# 10_-MAIN_POWER.net
KiCad netlist of a schematic drawn in Altium Designer
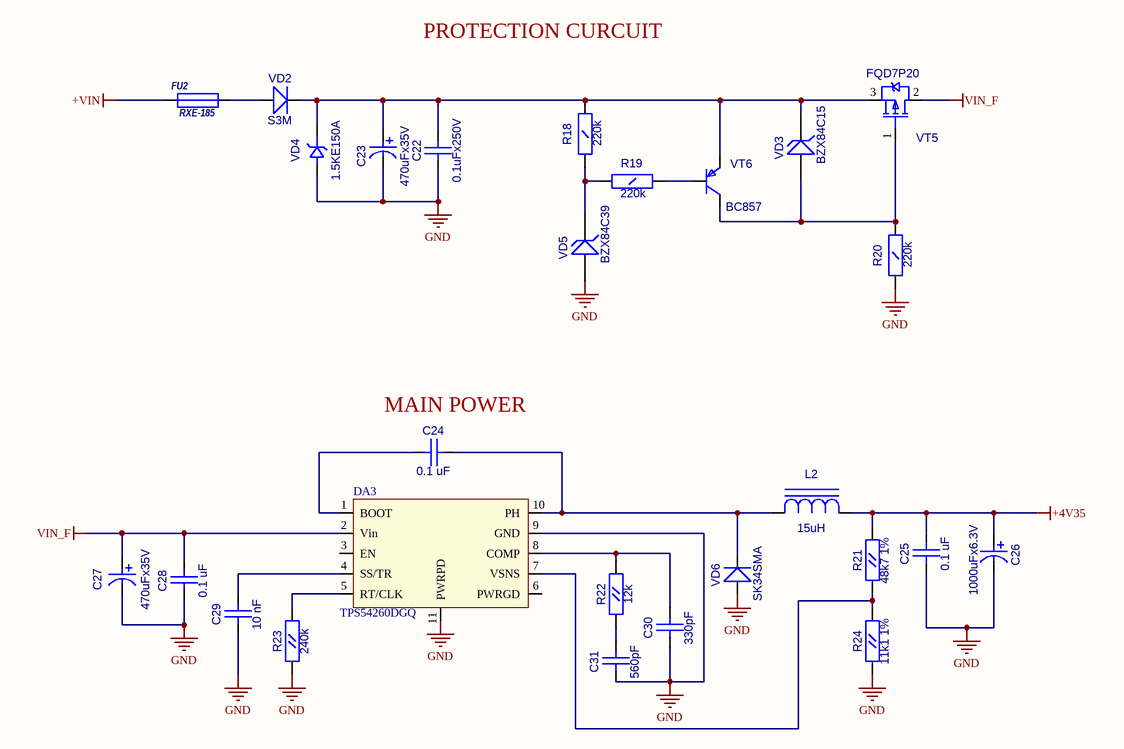
[diagram p0: [10]-MAIN_POWER.SchDoc]

(export (version "E")
  (design (tool "Eeschema 10.0.6"))
  (components
    (comp (ref "C22")
      (value "0.1uFx250V")
      (footprint "CC1206")
      (description "CC1206")
      (libsource (lib "gprs_modem_2") (part "CC1206"))
    )
    (comp (ref "C23")
      (value "470uFx35V")
      (footprint "CC16X10_CAP0.5(1)(Primary)")
      (description "CAP0.5(1)")
      (libsource (lib "gprs_modem_2") (part "CAP0.5(1)"))
    )
    (comp (ref "C24")
      (value "0.1 uF")
      (footprint "CC0603")
      (description "CC0603")
      (libsource (lib "gprs_modem_2") (part "CC0603"))
    )
    (comp (ref "C25")
      (value "0.1 uF")
      (footprint "CC0603")
      (description "CC0603")
      (libsource (lib "gprs_modem_2") (part "CC0603"))
    )
    (comp (ref "C26")
      (value "1000uFx6.3V")
      (footprint "CC8X3.5")
      (description "CAP0.35")
      (libsource (lib "gprs_modem_2") (part "CAP0.35"))
    )
    (comp (ref "C27")
      (value "470uFx35V")
      (footprint "CC16X10_CAP0.5(1)(Primary)")
      (description "CAP0.5(1)")
      (libsource (lib "gprs_modem_2") (part "CAP0.5(1)"))
    )
    (comp (ref "C28")
      (value "0.1 uF")
      (footprint "CC0603")
      (description "CC0603")
      (libsource (lib "gprs_modem_2") (part "CC0603"))
    )
    (comp (ref "C29")
      (value "10 nF")
      (footprint "CC0603")
      (description "CC0603")
      (libsource (lib "gprs_modem_2") (part "CC0603"))
    )
    (comp (ref "C30")
      (value "330pF")
      (footprint "CC0603")
      (description "CC0603")
      (libsource (lib "gprs_modem_2") (part "CC0603"))
    )
    (comp (ref "C31")
      (value "560pF")
      (footprint "CC0603")
      (description "CC0603")
      (libsource (lib "gprs_modem_2") (part "CC0603"))
    )
    (comp (ref "DA3")
      (value "TPS54260DGQ")
      (footprint "S-PDSO-G10")
      (libsource (lib "gprs_modem_2") (part "TPS54260DGQ"))
    )
    (comp (ref "FU2") (value "RXE-185") (footprint "RXE-185") (libsource (lib "fizik_lib") (part "RXE-185")))
    (comp (ref "L2")
      (value "15uH")
      (footprint "SDR0805")
      (description "SDR0805")
      (libsource (lib "gprs_modem_2") (part "SDR0805"))
    )
    (comp (ref "R18")
      (value "220k")
      (footprint "RC1206")
      (description "RC1206")
      (libsource (lib "fizik_lib") (part "RC1206"))
    )
    (comp (ref "R19")
      (value "220k")
      (footprint "RC1206")
      (description "RC1206")
      (libsource (lib "fizik_lib") (part "RC1206"))
    )
    (comp (ref "R20")
      (value "220k")
      (footprint "RC1206")
      (description "RC1206")
      (libsource (lib "fizik_lib") (part "RC1206"))
    )
    (comp (ref "R21")
      (value "48k7 1%")
      (footprint "RC0603")
      (description "RC0603")
      (libsource (lib "gprs_modem_2") (part "RC0603"))
    )
    (comp (ref "R22")
      (value "12k")
      (footprint "RC0603")
      (description "RC0603")
      (libsource (lib "gprs_modem_2") (part "RC0603"))
    )
    (comp (ref "R23")
      (value "240k")
      (footprint "RC0603")
      (description "RC0603")
      (libsource (lib "gprs_modem_2") (part "RC0603"))
    )
    (comp (ref "R24")
      (value "11k1 1%")
      (footprint "RC0603")
      (description "RC0603")
      (libsource (lib "gprs_modem_2") (part "RC0603"))
    )
    (comp (ref "VD2")
      (value "S3M")
      (footprint "SMC")
      (description "Schottky Rectifier")
      (libsource (lib "fizik_lib") (part "S3A"))
    )
    (comp (ref "VD3")
      (value "BZX84C15")
      (footprint "SOT-23(123)")
      (description "Zener Voltage Regulator Diode")
      (libsource (lib "fizik_lib") (part "BZX84"))
    )
    (comp (ref "VD4")
      (value "1.5KE150A")
      (footprint "DO-201")
      (description "1.5KE")
      (libsource (lib "gprs_modem") (part "1.5KE"))
    )
    (comp (ref "VD5")
      (value "BZX84C39")
      (footprint "SOT-23(123)")
      (description "Zener Voltage Regulator Diode")
      (libsource (lib "fizik_lib") (part "BZX84"))
    )
    (comp (ref "VD6")
      (value "SK34SMA")
      (footprint "SMA")
      (description "Schottky Rectifier")
      (libsource (lib "gprs_modem") (part "SK34SMA"))
    )
    (comp (ref "VT5")
      (value "FQD7P20")
      (footprint "D-PAK(TO-252AA)")
      (description "HEXFET Power MOSFET")
      (libsource (lib "gprs_modem_2") (part "IRFR9220"))
    )
    (comp (ref "VT6")
      (value "BC857")
      (footprint "SOT-23(123)")
      (description "PNP 100ma transistor")
      (libsource (lib "gprs_modem_2") (part "BC857B"))
    )
  )
  (nets
    (net (code "1") (name "+4V35") (class "Default")
      (node (ref "C25") (pin "1") (pinfunction "A_1") (pintype "passive"))
      (node (ref "C26") (pin "1") (pintype "passive"))
      (node (ref "L2") (pin "2") (pinfunction "A_2") (pintype "passive"))
      (node (ref "R21") (pin "2") (pinfunction "B_2") (pintype "passive"))
    )
    (net (code "2") (name "+VIN") (class "Default") (node (ref "FU2") (pin "1") (pintype "passive")))
    (net (code "3") (name "GND") (class "Default")
      (node (ref "C22") (pin "1") (pinfunction "A_1") (pintype "passive"))
      (node (ref "C23") (pin "1") (pintype "passive"))
      (node (ref "C25") (pin "2") (pinfunction "B_2") (pintype "passive"))
      (node (ref "C26") (pin "2") (pintype "passive"))
      (node (ref "C27") (pin "1") (pintype "passive"))
      (node (ref "C28") (pin "2") (pinfunction "B_2") (pintype "passive"))
      (node (ref "C29") (pin "2") (pinfunction "B_2") (pintype "passive"))
      (node (ref "C30") (pin "2") (pinfunction "B_2") (pintype "passive"))
      (node (ref "C31") (pin "2") (pinfunction "B_2") (pintype "passive"))
      (node (ref "DA3") (pin "11") (pinfunction "PWRPD_11") (pintype "passive"))
      (node (ref "DA3") (pin "9") (pinfunction "GND_9") (pintype "passive"))
      (node (ref "R20") (pin "1") (pinfunction "A_1") (pintype "passive"))
      (node (ref "R23") (pin "1") (pinfunction "A_1") (pintype "passive"))
      (node (ref "R24") (pin "1") (pinfunction "A_1") (pintype "passive"))
      (node (ref "VD4") (pin "1") (pinfunction "A_1") (pintype "passive"))
      (node (ref "VD5") (pin "1") (pinfunction "A_1") (pintype "passive"))
      (node (ref "VD6") (pin "1") (pinfunction "A_1") (pintype "passive"))
    )
    (net (code "4") (name "Net-(C22-B)") (class "Default")
      (node (ref "C22") (pin "2") (pinfunction "B_2") (pintype "passive"))
      (node (ref "C23") (pin "2") (pintype "passive"))
      (node (ref "R18") (pin "2") (pinfunction "B_2") (pintype "passive"))
      (node (ref "VD2") (pin "2") (pinfunction "K_2") (pintype "passive"))
      (node (ref "VD3") (pin "3") (pinfunction "K_3") (pintype "passive"))
      (node (ref "VD4") (pin "2") (pinfunction "K_2") (pintype "passive"))
      (node (ref "VT5") (pin "3") (pinfunction "S_3") (pintype "passive"))
      (node (ref "VT6") (pin "2") (pinfunction "E_2") (pintype "passive"))
    )
    (net (code "5") (name "Net-(C24-A)") (class "Default")
      (node (ref "C24") (pin "1") (pinfunction "A_1") (pintype "passive"))
      (node (ref "DA3") (pin "10") (pinfunction "PH_10") (pintype "passive"))
      (node (ref "L2") (pin "1") (pinfunction "C_1") (pintype "passive"))
      (node (ref "VD6") (pin "2") (pinfunction "K_2") (pintype "passive"))
    )
    (net (code "6") (name "Net-(C24-B)") (class "Default")
      (node (ref "C24") (pin "2") (pinfunction "B_2") (pintype "passive"))
      (node (ref "DA3") (pin "1") (pinfunction "BOOT_1") (pintype "passive"))
    )
    (net (code "7") (name "Net-(C29-A)") (class "Default")
      (node (ref "C29") (pin "1") (pinfunction "A_1") (pintype "passive"))
      (node (ref "DA3") (pin "4") (pinfunction "SS/TR_4") (pintype "passive"))
    )
    (net (code "8") (name "Net-(C30-A)") (class "Default")
      (node (ref "C30") (pin "1") (pinfunction "A_1") (pintype "passive"))
      (node (ref "DA3") (pin "8") (pinfunction "COMP_8") (pintype "passive"))
      (node (ref "R22") (pin "2") (pinfunction "B_2") (pintype "passive"))
    )
    (net (code "9") (name "Net-(C31-A)") (class "Default")
      (node (ref "C31") (pin "1") (pinfunction "A_1") (pintype "passive"))
      (node (ref "R22") (pin "1") (pinfunction "A_1") (pintype "passive"))
    )
    (net (code "10") (name "Net-(DA3-RT{slash}CLK)") (class "Default")
      (node (ref "DA3") (pin "5") (pinfunction "RT/CLK_5") (pintype "passive"))
      (node (ref "R23") (pin "2") (pinfunction "B_2") (pintype "passive"))
    )
    (net (code "11") (name "Net-(DA3-VSNS)") (class "Default")
      (node (ref "DA3") (pin "7") (pinfunction "VSNS_7") (pintype "passive"))
      (node (ref "R21") (pin "1") (pinfunction "A_1") (pintype "passive"))
      (node (ref "R24") (pin "2") (pinfunction "B_2") (pintype "passive"))
    )
    (net (code "12") (name "Net-(R18-A)") (class "Default")
      (node (ref "R18") (pin "1") (pinfunction "A_1") (pintype "passive"))
      (node (ref "R19") (pin "1") (pinfunction "A_1") (pintype "passive"))
      (node (ref "VD5") (pin "3") (pinfunction "K_3") (pintype "passive"))
    )
    (net (code "13") (name "Net-(R19-B)") (class "Default")
      (node (ref "R19") (pin "2") (pinfunction "B_2") (pintype "passive"))
      (node (ref "VT6") (pin "1") (pinfunction "B_1") (pintype "passive"))
    )
    (net (code "14") (name "Net-(R20-B)") (class "Default")
      (node (ref "R20") (pin "2") (pinfunction "B_2") (pintype "passive"))
      (node (ref "VD3") (pin "1") (pinfunction "A_1") (pintype "passive"))
      (node (ref "VT5") (pin "1") (pinfunction "G_1") (pintype "passive"))
      (node (ref "VT6") (pin "3") (pinfunction "C_3") (pintype "passive"))
    )
    (net (code "15") (name "Net-(VD2-A)") (class "Default")
      (node (ref "FU2") (pin "2") (pintype "passive"))
      (node (ref "VD2") (pin "1") (pinfunction "A_1") (pintype "passive"))
    )
    (net (code "16") (name "VIN_F") (class "Default")
      (node (ref "C27") (pin "2") (pintype "passive"))
      (node (ref "C28") (pin "1") (pinfunction "A_1") (pintype "passive"))
      (node (ref "DA3") (pin "2") (pinfunction "Vin_2") (pintype "passive"))
      (node (ref "VT5") (pin "2") (pinfunction "D_2") (pintype "passive"))
    )
    (net (code "17") (name "unconnected-(DA3-EN-Pad3)") (class "Default")
      (node (ref "DA3") (pin "3") (pinfunction "EN_3") (pintype "passive"))
    )
    (net (code "18") (name "unconnected-(DA3-PWRGD-Pad6)") (class "Default")
      (node (ref "DA3") (pin "6") (pinfunction "PWRGD_6") (pintype "passive"))
    )
  )
)
